# PowerBoard.net
KiCad netlist of a schematic drawn in Altium Designer
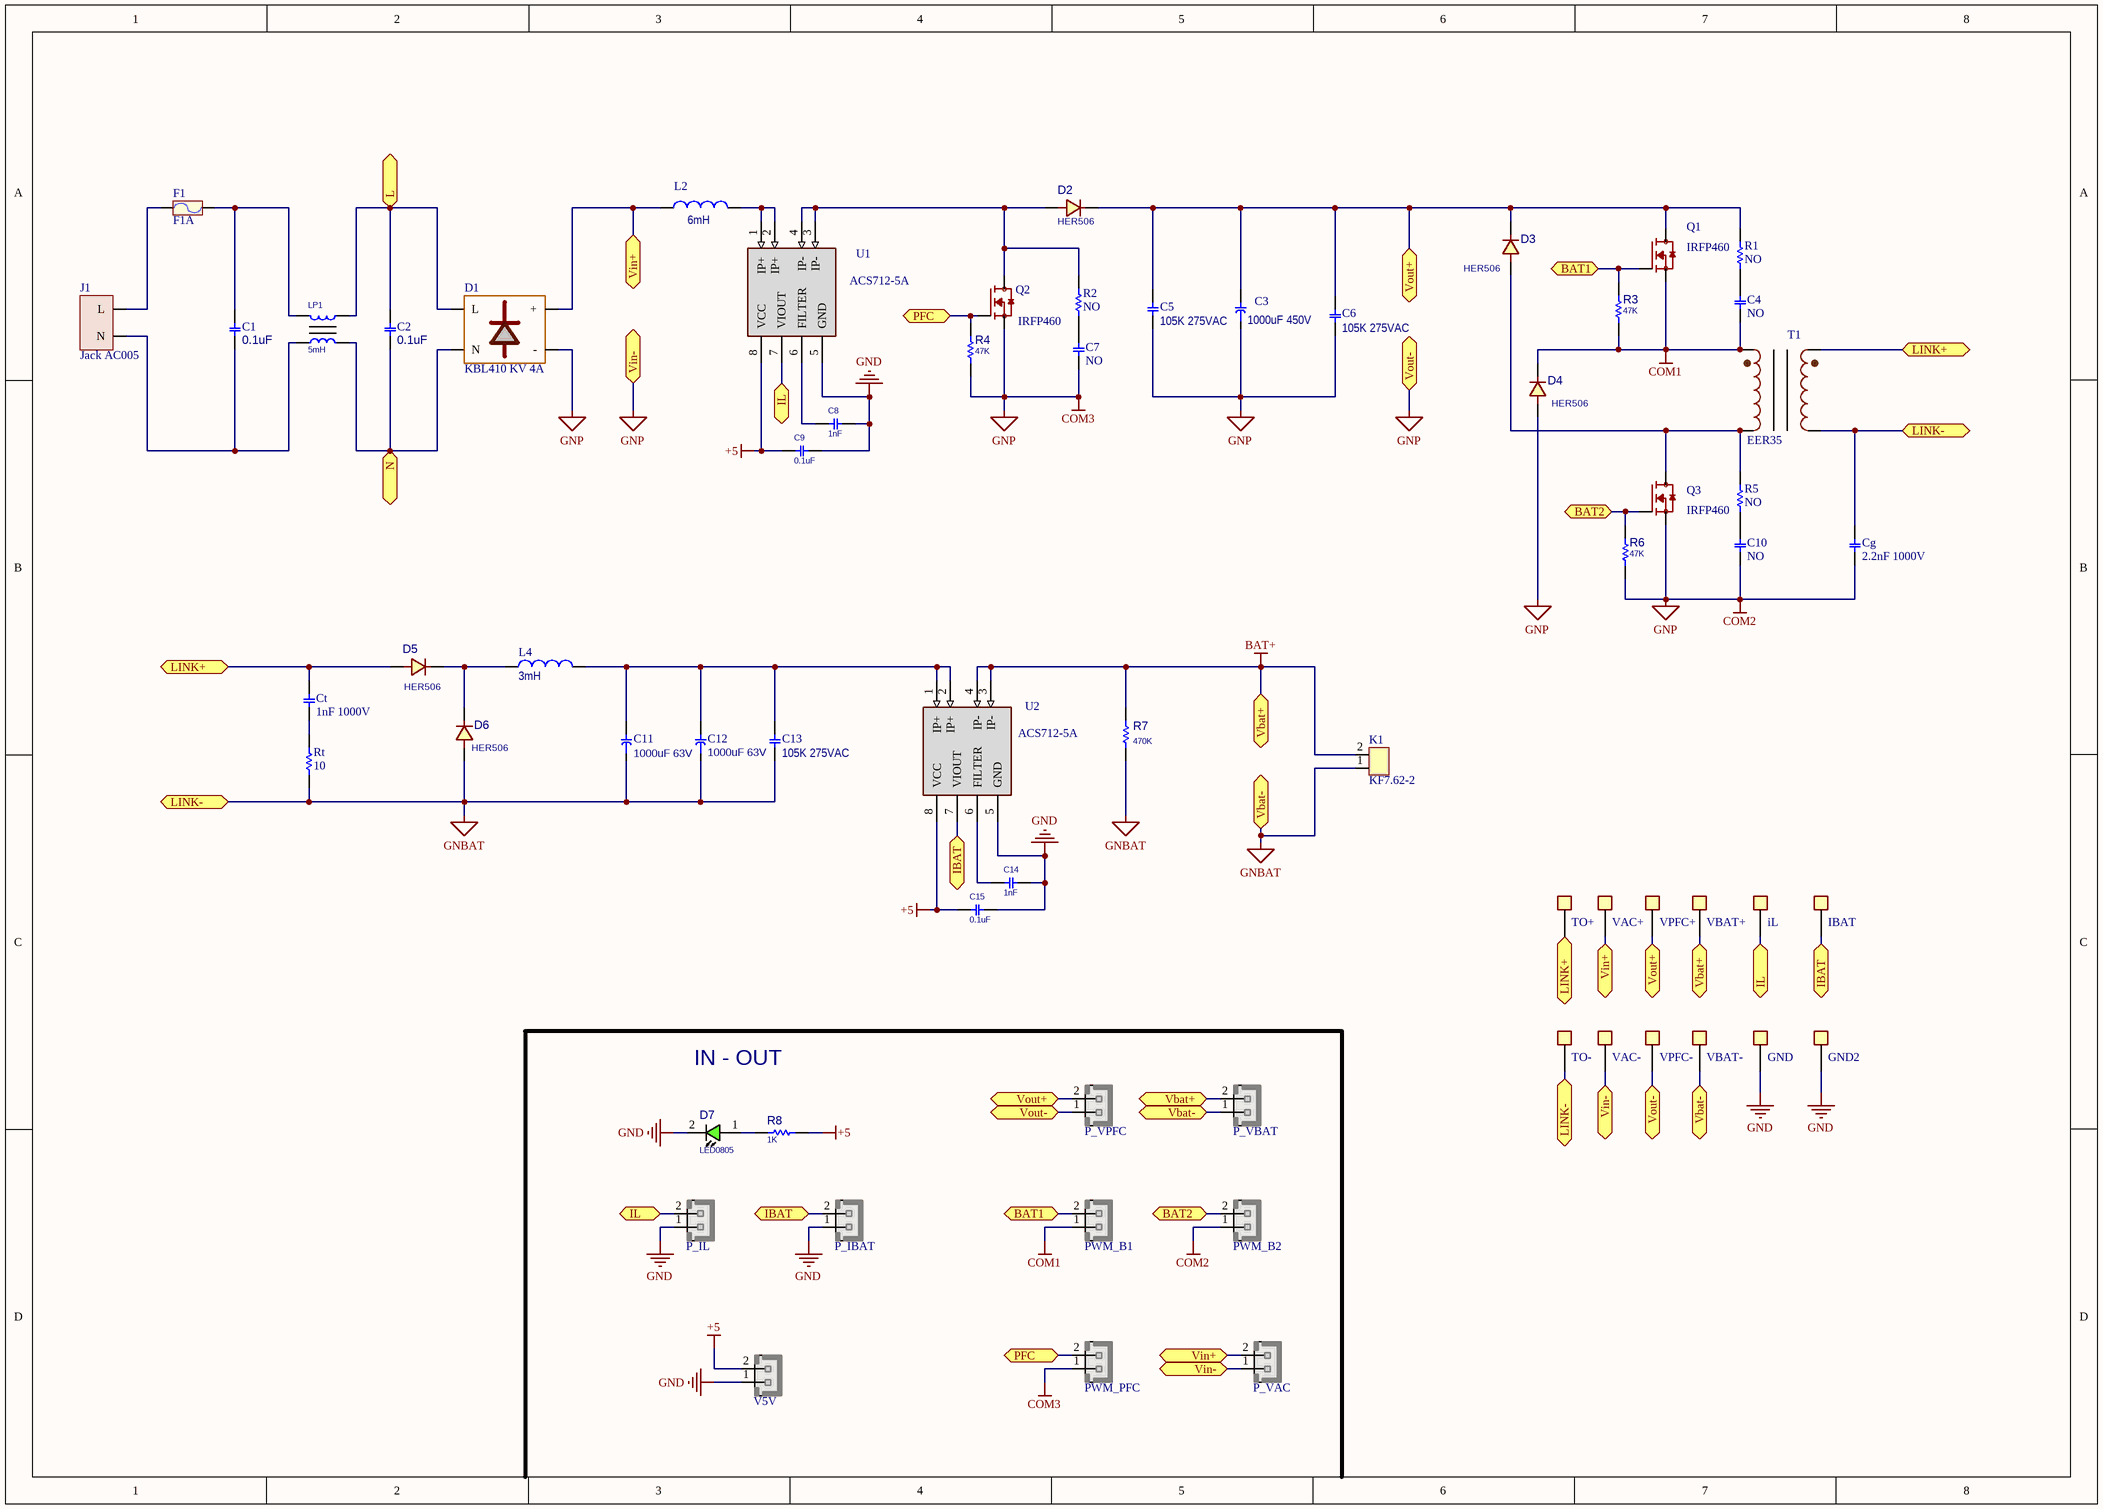
[diagram p0: PowerBoard.SchDoc]

(export (version "E")
  (design (tool "Eeschema 10.0.6"))
  (components
    (comp (ref "C1")
      (value "0.1uF")
      (footprint "CAP P=15MM")
      (description "100nF 104J 275VAC")
      (fields (field (name "COPYRIGHT") "VanDungEvn"))
      (libsource (lib "IoT") (part "CAP Keo"))
    )
    (comp (ref "C2")
      (value "0.1uF")
      (footprint "CAP P=15MM")
      (description "100nF 104J 275VAC")
      (fields (field (name "COPYRIGHT") "VanDungEvn"))
      (libsource (lib "IoT") (part "CAP Keo"))
    )
    (comp (ref "C3")
      (value "1000uF 450V")
      (footprint "cap dxl 35x45")
      (description "CAP DIP")
      (libsource (lib "IoT") (part "CAP DIP"))
    )
    (comp (ref "C4")
      (value "NO")
      (footprint "CAP CBB22 100nF/630V")
      (description "CAP Keo")
      (fields (field (name "COPYRIGHT") "VanDungEvn"))
      (libsource (lib "IoT") (part "CAP Keo"))
    )
    (comp (ref "C5")
      (value "105K 275VAC")
      (footprint "CAP P=22.5mm Len=26.5")
      (description "CAP Keo")
      (fields (field (name "COPYRIGHT") "VanDungEvn"))
      (libsource (lib "IoT") (part "CAP Keo"))
    )
    (comp (ref "C6")
      (value "105K 275VAC")
      (footprint "CAP P=22.5mm Len=26.5")
      (description "CAP Keo")
      (fields (field (name "COPYRIGHT") "VanDungEvn"))
      (libsource (lib "IoT") (part "CAP Keo"))
    )
    (comp (ref "C7")
      (value "NO")
      (footprint "CAP CBB22 100nF/630V")
      (description "CAP Keo")
      (fields (field (name "COPYRIGHT") "VanDungEvn"))
      (libsource (lib "IoT") (part "CAP Keo"))
    )
    (comp (ref "C8")
      (value "1nF")
      (footprint "cap_0805")
      (description "CAP SMD")
      (fields (field (name "MANF_P#") "MANF_PART#"))
      (libsource (lib "IoT") (part "CAP SMD"))
    )
    (comp (ref "C9")
      (value "0.1uF")
      (footprint "cap_0805")
      (description "CAP SMD")
      (fields (field (name "MANF_P#") "MANF_PART#"))
      (libsource (lib "IoT") (part "CAP SMD"))
    )
    (comp (ref "C10")
      (value "NO")
      (footprint "CAP CBB22 100nF/630V")
      (description "CAP Keo")
      (fields (field (name "COPYRIGHT") "VanDungEvn"))
      (libsource (lib "IoT") (part "CAP Keo"))
    )
    (comp (ref "C11")
      (value "1000uF 63V")
      (footprint "CAP DxL 16x25")
      (description "CAP DIP")
      (libsource (lib "IoT") (part "CAP DIP"))
    )
    (comp (ref "C12")
      (value "1000uF 63V")
      (footprint "CAP DxL 16x25")
      (description "CAP DIP")
      (libsource (lib "IoT") (part "CAP DIP"))
    )
    (comp (ref "C13")
      (value "105K 275VAC")
      (footprint "CAP P=22.5mm Len=26.5")
      (description "CAP Keo")
      (fields (field (name "COPYRIGHT") "VanDungEvn"))
      (libsource (lib "IoT") (part "CAP Keo"))
    )
    (comp (ref "C14")
      (value "1nF")
      (footprint "cap_0805")
      (description "CAP SMD")
      (fields (field (name "MANF_P#") "MANF_PART#"))
      (libsource (lib "IoT") (part "CAP SMD"))
    )
    (comp (ref "C15")
      (value "0.1uF")
      (footprint "cap_0805")
      (description "CAP SMD")
      (fields (field (name "MANF_P#") "MANF_PART#"))
      (libsource (lib "IoT") (part "CAP SMD"))
    )
    (comp (ref "Cg")
      (value "2.2nF 1000V")
      (footprint "CAP CERAMIC Blue")
      (description "Tu Gom Xanh 2.2nF 1000V")
      (fields (field (name "COPYRIGHT") "VanDungEvn"))
      (libsource (lib "IoT") (part "CAP Keo"))
    )
    (comp (ref "Ct")
      (value "1nF 1000V")
      (footprint "CAP CERAMIC Blue")
      (description "Tu Gom Xanh 1nF 1000V")
      (fields (field (name "COPYRIGHT") "VanDungEvn"))
      (libsource (lib "IoT") (part "CAP Keo"))
    )
    (comp (ref "D1")
      (value "KBL410 KV 4A")
      (footprint "SIP-4 KBL")
      (description "Diode Bridge 1KV 4A")
      (libsource (lib "IoT") (part "Diode Bridge"))
    )
    (comp (ref "D2")
      (value "HER506")
      (footprint "DIODE DO-201AD")
      (description "DIODE DIP")
      (fields (field (name "MANF") "Kingtronics") (field (name "MANF_P#") "M7"))
      (libsource (lib "IoT") (part "DIODE DIP"))
    )
    (comp (ref "D3")
      (value "HER506")
      (footprint "DIODE DO-201AD")
      (description "DIODE DIP")
      (fields (field (name "MANF") "Kingtronics") (field (name "MANF_P#") "M7"))
      (libsource (lib "IoT") (part "DIODE DIP"))
    )
    (comp (ref "D4")
      (value "HER506")
      (footprint "DIODE DO-201AD")
      (description "DIODE DIP")
      (fields (field (name "MANF") "Kingtronics") (field (name "MANF_P#") "M7"))
      (libsource (lib "IoT") (part "DIODE DIP"))
    )
    (comp (ref "D5")
      (value "HER506")
      (footprint "DIODE DO-201AD")
      (description "DIODE DIP")
      (fields (field (name "MANF") "Kingtronics") (field (name "MANF_P#") "M7"))
      (libsource (lib "IoT") (part "DIODE DIP"))
    )
    (comp (ref "D6")
      (value "HER506")
      (footprint "DIODE DO-201AD")
      (description "DIODE DIP")
      (fields (field (name "MANF") "Kingtronics") (field (name "MANF_P#") "M7"))
      (libsource (lib "IoT") (part "DIODE DIP"))
    )
    (comp (ref "D7")
      (value "LED0805")
      (footprint "LED0805")
      (description "LED, SMD, 0805")
      (fields (field (name "MANF") "MANF") (field (name "MANF_P#") "MANF_PART#"))
      (libsource (lib "IoT") (part "LED_SMD_0805"))
    )
    (comp (ref "F1")
      (value "F1A")
      (footprint "FUSE")
      (description "Cau Chi ong Thuy Tinh 3A 5x20mm")
      (fields (field (name "DESIGNED BY") "VanDungEvn"))
      (libsource (lib "IoT") (part "Fuse"))
    )
    (comp (ref "GND")
      (value "test PCB")
      (footprint "Tp_black_1p")
      (description "testpin")
      (libsource (lib "IoT") (part "test PCB"))
    )
    (comp (ref "GND2")
      (value "test PCB")
      (footprint "Tp_black_1p")
      (description "testpin")
      (libsource (lib "IoT") (part "test PCB"))
    )
    (comp (ref "IBAT")
      (value "test PCB")
      (footprint "tp_red_1p")
      (description "testpin")
      (libsource (lib "IoT") (part "test PCB"))
    )
    (comp (ref "iL")
      (value "test PCB")
      (footprint "tp_red_1p")
      (description "testpin")
      (libsource (lib "IoT") (part "test PCB"))
    )
    (comp (ref "J1")
      (value "Jack AC005")
      (footprint "AC005")
      (description "AC005 5A")
      (libsource (lib "IoT") (part "Jack AC"))
    )
    (comp (ref "K1")
      (value "KF7.62-2")
      (footprint "KF_2PIN")
      (description "KF_2PIN")
      (libsource (lib "IoT") (part "KF_2PIN"))
    )
    (comp (ref "L2")
      (value "6mH")
      (footprint "IND 40P")
      (description "IND DIP")
      (fields
        (field (name "MANUFACTURER") "Murata")
        (field (name "MANUFACTURER PART NUMBER") "LQW15AN2N2G80D")
      )
      (libsource (lib "IoT") (part "IND DIP"))
    )
    (comp (ref "L4")
      (value "3mH")
      (footprint "IND 40P")
      (description "IND DIP")
      (fields
        (field (name "MANUFACTURER") "Murata")
        (field (name "MANUFACTURER PART NUMBER") "LQW15AN2N2G80D")
      )
      (libsource (lib "IoT") (part "IND DIP"))
    )
    (comp (ref "LP1")
      (value "5mH")
      (footprint "Filter Inductor")
      (description "5mH UU9.8-502")
      (fields (field (name "MANF") "Coilcraft") (field (name "MANF_P#") "XAL1030-301MEC"))
      (libsource (lib "IoT") (part "IND Filter 15mH"))
    )
    (comp (ref "PWM_B1")
      (value "HHDR_2")
      (footprint "VH-2")
      (description "VH-2")
      (libsource (lib "IoT") (part "VH-2"))
    )
    (comp (ref "PWM_B2")
      (value "HHDR_2")
      (footprint "VH-2")
      (description "VH-2")
      (libsource (lib "IoT") (part "VH-2"))
    )
    (comp (ref "PWM_PFC")
      (value "HHDR_2")
      (footprint "VH-2")
      (description "VH-2")
      (libsource (lib "IoT") (part "VH-2"))
    )
    (comp (ref "P_IBAT")
      (value "HHDR_2")
      (footprint "XH_2")
      (description "XH 2 JST-XH pitch: 2.5mm")
      (libsource (lib "IoT") (part "XH_2"))
    )
    (comp (ref "P_IL")
      (value "HHDR_2")
      (footprint "XH_2")
      (description "XH 2 JST-XH pitch: 2.5mm")
      (libsource (lib "IoT") (part "XH_2"))
    )
    (comp (ref "P_VAC")
      (value "HHDR_2")
      (footprint "VH-2")
      (description "VH-2")
      (libsource (lib "IoT") (part "VH-2"))
    )
    (comp (ref "P_VBAT")
      (value "HHDR_2")
      (footprint "VH-2")
      (description "VH-2")
      (libsource (lib "IoT") (part "VH-2"))
    )
    (comp (ref "P_VPFC")
      (value "HHDR_2")
      (footprint "VH-2")
      (description "VH-2")
      (libsource (lib "IoT") (part "VH-2"))
    )
    (comp (ref "Q1")
      (value "IRFP460")
      (footprint "TO-247 - HS342512")
      (description "MOSFET N-Channel 500 V 20A (Tc) 280W (Tc) Through Hole TO-247AC")
      (fields (field (name "MF") "Vishay Siliconix"))
      (libsource (lib "IoT") (part "MOSFET IRFP460"))
    )
    (comp (ref "Q2")
      (value "IRFP460")
      (footprint "TO-247 - HS342512")
      (description "MOSFET N-Channel 500 V 20A (Tc) 280W (Tc) Through Hole TO-247AC")
      (fields (field (name "MF") "Vishay Siliconix"))
      (libsource (lib "IoT") (part "MOSFET IRFP460"))
    )
    (comp (ref "Q3")
      (value "IRFP460")
      (footprint "TO-247 - HS342512")
      (description "MOSFET N-Channel 500 V 20A (Tc) 280W (Tc) Through Hole TO-247AC")
      (fields (field (name "MF") "Vishay Siliconix"))
      (libsource (lib "IoT") (part "MOSFET IRFP460"))
    )
    (comp (ref "R1")
      (value "NO")
      (footprint "R-2W")
      (description "RES DIP")
      (libsource (lib "IoT") (part "RES DIP"))
    )
    (comp (ref "R2")
      (value "NO")
      (footprint "R-2W")
      (description "RES DIP")
      (libsource (lib "IoT") (part "RES DIP"))
    )
    (comp (ref "R3")
      (value "47K")
      (footprint "R0805")
      (description "RES SMD")
      (fields (field (name "MANF_P#") "WSLP0805R0100FEA") (field (name "MANF") "VISHAY"))
      (libsource (lib "IoT") (part "RES SMD"))
    )
    (comp (ref "R4")
      (value "47K")
      (footprint "R0805")
      (description "RES SMD")
      (fields (field (name "MANF_P#") "WSLP0805R0100FEA") (field (name "MANF") "VISHAY"))
      (libsource (lib "IoT") (part "RES SMD"))
    )
    (comp (ref "R5")
      (value "NO")
      (footprint "R-2W")
      (description "RES DIP")
      (libsource (lib "IoT") (part "RES DIP"))
    )
    (comp (ref "R6")
      (value "47K")
      (footprint "R0805")
      (description "RES SMD")
      (fields (field (name "MANF_P#") "WSLP0805R0100FEA") (field (name "MANF") "VISHAY"))
      (libsource (lib "IoT") (part "RES SMD"))
    )
    (comp (ref "R7")
      (value "470K")
      (footprint "R1206")
      (description "RES SMD")
      (fields (field (name "MANF_P#") "WSLP0805R0100FEA") (field (name "MANF") "VISHAY"))
      (libsource (lib "IoT") (part "RES SMD"))
    )
    (comp (ref "R8")
      (value "1K")
      (footprint "R0805")
      (description "RES SMD")
      (fields (field (name "MANF_P#") "WSLP0805R0100FEA") (field (name "MANF") "VISHAY"))
      (libsource (lib "IoT") (part "RES SMD"))
    )
    (comp (ref "Rt")
      (value "10")
      (footprint "R1/4W4")
      (description "10 ohm, 1W")
      (libsource (lib "IoT") (part "RES DIP"))
    )
    (comp (ref "T1")
      (value "EER35")
      (footprint "Pulse Transformer")
      (description "Pulse Transformer")
      (libsource (lib "IoT") (part "Pulse Transformer"))
    )
    (comp (ref "TO+")
      (value "test PCB")
      (footprint "tp_red_1p")
      (description "testpin")
      (libsource (lib "IoT") (part "test PCB"))
    )
    (comp (ref "TO-")
      (value "test PCB")
      (footprint "Tp_black_1p")
      (description "testpin")
      (libsource (lib "IoT") (part "test PCB"))
    )
    (comp (ref "U1")
      (value "ACS712-5A")
      (footprint "IoT:ACS712")
      (description "ACS712ELCTR-T")
      (fields (field (name "MF") "{'manufacturer': u'Allegro'}") (field (name "MP") "ACS712ELCTR-20A-T"))
      (libsource (lib "IoT") (part "ACS712ELCTR-T"))
    )
    (comp (ref "U2")
      (value "ACS712-5A")
      (footprint "IoT:ACS712")
      (description "ACS712ELCTR-T")
      (fields (field (name "MF") "{'manufacturer': u'Allegro'}") (field (name "MP") "ACS712ELCTR-20A-T"))
      (libsource (lib "IoT") (part "ACS712ELCTR-T"))
    )
    (comp (ref "V5V")
      (value "HHDR_2")
      (footprint "VH-2")
      (description "VH-2")
      (libsource (lib "IoT") (part "VH-2"))
    )
    (comp (ref "VAC+")
      (value "test PCB")
      (footprint "tp_red_1p")
      (description "testpin")
      (libsource (lib "IoT") (part "test PCB"))
    )
    (comp (ref "VAC-")
      (value "test PCB")
      (footprint "Tp_black_1p")
      (description "testpin")
      (libsource (lib "IoT") (part "test PCB"))
    )
    (comp (ref "VBAT+")
      (value "test PCB")
      (footprint "tp_red_1p")
      (description "testpin")
      (libsource (lib "IoT") (part "test PCB"))
    )
    (comp (ref "VBAT-")
      (value "test PCB")
      (footprint "Tp_black_1p")
      (description "testpin")
      (libsource (lib "IoT") (part "test PCB"))
    )
    (comp (ref "VPFC+")
      (value "test PCB")
      (footprint "tp_red_1p")
      (description "testpin")
      (libsource (lib "IoT") (part "test PCB"))
    )
    (comp (ref "VPFC-")
      (value "test PCB")
      (footprint "Tp_black_1p")
      (description "testpin")
      (libsource (lib "IoT") (part "test PCB"))
    )
  )
  (nets
    (net (code "1") (name "+5") (class "Default")
      (node (ref "C15") (pin "2") (pinfunction "2_2") (pintype "passive"))
      (node (ref "C9") (pin "2") (pinfunction "2_2") (pintype "passive"))
      (node (ref "R8") (pin "2") (pinfunction "2_2") (pintype "passive"))
      (node (ref "U1") (pin "8") (pinfunction "VCC_8") (pintype "power_in"))
      (node (ref "U2") (pin "8") (pinfunction "VCC_8") (pintype "power_in"))
      (node (ref "V5V") (pin "2") (pinfunction "2_2") (pintype "passive"))
    )
    (net (code "2") (name "/BAT1") (class "Default")
      (node (ref "PWM_B1") (pin "2") (pinfunction "2_2") (pintype "passive"))
      (node (ref "Q1") (pin "1") (pinfunction "G_1") (pintype "passive"))
      (node (ref "R3") (pin "1") (pinfunction "1_1") (pintype "passive"))
    )
    (net (code "3") (name "/BAT2") (class "Default")
      (node (ref "PWM_B2") (pin "2") (pinfunction "2_2") (pintype "passive"))
      (node (ref "Q3") (pin "1") (pinfunction "G_1") (pintype "passive"))
      (node (ref "R6") (pin "1") (pinfunction "1_1") (pintype "passive"))
    )
    (net (code "4") (name "/IBAT") (class "Default")
      (node (ref "IBAT") (pin "1") (pinfunction "1_1") (pintype "power_in"))
      (node (ref "P_IBAT") (pin "2") (pinfunction "2_2") (pintype "passive"))
      (node (ref "U2") (pin "7") (pinfunction "VIOUT_7") (pintype "power_in"))
    )
    (net (code "5") (name "/IL") (class "Default")
      (node (ref "P_IL") (pin "2") (pinfunction "2_2") (pintype "passive"))
      (node (ref "U1") (pin "7") (pinfunction "VIOUT_7") (pintype "power_in"))
      (node (ref "iL") (pin "1") (pinfunction "1_1") (pintype "power_in"))
    )
    (net (code "6") (name "/L") (class "Default")
      (node (ref "C2") (pin "2") (pinfunction "2_2") (pintype "passive"))
      (node (ref "D1") (pin "2") (pinfunction "L_2") (pintype "passive"))
      (node (ref "LP1") (pin "2") (pinfunction "2_2") (pintype "passive"))
    )
    (net (code "7") (name "/LINK+") (class "Default")
      (node (ref "Ct") (pin "2") (pinfunction "2_2") (pintype "passive"))
      (node (ref "D5") (pin "1") (pinfunction "1_1") (pintype "passive"))
      (node (ref "T1") (pin "9") (pinfunction "9_9") (pintype "passive"))
      (node (ref "TO+") (pin "1") (pinfunction "1_1") (pintype "power_in"))
    )
    (net (code "8") (name "/N") (class "Default")
      (node (ref "C2") (pin "1") (pinfunction "1_1") (pintype "passive"))
      (node (ref "D1") (pin "3") (pinfunction "N_3") (pintype "passive"))
      (node (ref "LP1") (pin "4") (pinfunction "4_4") (pintype "passive"))
    )
    (net (code "9") (name "/PFC") (class "Default")
      (node (ref "PWM_PFC") (pin "2") (pinfunction "2_2") (pintype "passive"))
      (node (ref "Q2") (pin "1") (pinfunction "G_1") (pintype "passive"))
      (node (ref "R4") (pin "2") (pinfunction "2_2") (pintype "passive"))
    )
    (net (code "10") (name "/Vin+") (class "Default")
      (node (ref "D1") (pin "1") (pinfunction "+_1") (pintype "passive"))
      (node (ref "L2") (pin "1") (pinfunction "1_1") (pintype "passive"))
      (node (ref "P_VAC") (pin "2") (pinfunction "2_2") (pintype "passive"))
      (node (ref "VAC+") (pin "1") (pinfunction "1_1") (pintype "power_in"))
    )
    (net (code "11") (name "/Vout+") (class "Default")
      (node (ref "C3") (pin "1") (pinfunction "1_1") (pintype "passive"))
      (node (ref "C5") (pin "2") (pinfunction "2_2") (pintype "passive"))
      (node (ref "C6") (pin "2") (pinfunction "2_2") (pintype "passive"))
      (node (ref "D2") (pin "2") (pinfunction "2_2") (pintype "passive"))
      (node (ref "D3") (pin "2") (pinfunction "2_2") (pintype "passive"))
      (node (ref "P_VPFC") (pin "2") (pinfunction "2_2") (pintype "passive"))
      (node (ref "Q1") (pin "2") (pinfunction "D_2") (pintype "passive"))
      (node (ref "R1") (pin "2") (pinfunction "2_2") (pintype "passive"))
      (node (ref "VPFC+") (pin "1") (pinfunction "1_1") (pintype "power_in"))
    )
    (net (code "12") (name "BAT+") (class "Default")
      (node (ref "K1") (pin "2") (pinfunction "2_2") (pintype "passive"))
      (node (ref "P_VBAT") (pin "2") (pinfunction "2_2") (pintype "passive"))
      (node (ref "R7") (pin "2") (pinfunction "2_2") (pintype "passive"))
      (node (ref "U2") (pin "3") (pinfunction "IP-_3") (pintype "input"))
      (node (ref "U2") (pin "4") (pinfunction "IP-_4") (pintype "input"))
      (node (ref "VBAT+") (pin "1") (pinfunction "1_1") (pintype "power_in"))
    )
    (net (code "13") (name "COM1") (class "Default")
      (node (ref "C4") (pin "1") (pinfunction "1_1") (pintype "passive"))
      (node (ref "D4") (pin "2") (pinfunction "2_2") (pintype "passive"))
      (node (ref "PWM_B1") (pin "1") (pinfunction "1_1") (pintype "passive"))
      (node (ref "Q1") (pin "3") (pinfunction "S_3") (pintype "passive"))
      (node (ref "R3") (pin "2") (pinfunction "2_2") (pintype "passive"))
      (node (ref "T1") (pin "2") (pinfunction "2_2") (pintype "passive"))
    )
    (net (code "14") (name "COM2") (class "Default")
      (node (ref "C10") (pin "1") (pinfunction "1_1") (pintype "passive"))
      (node (ref "C3") (pin "2") (pinfunction "2_2") (pintype "passive"))
      (node (ref "C5") (pin "1") (pinfunction "1_1") (pintype "passive"))
      (node (ref "C6") (pin "1") (pinfunction "1_1") (pintype "passive"))
      (node (ref "C7") (pin "1") (pinfunction "1_1") (pintype "passive"))
      (node (ref "Cg") (pin "1") (pinfunction "1_1") (pintype "passive"))
      (node (ref "D1") (pin "4") (pinfunction "-_4") (pintype "passive"))
      (node (ref "D4") (pin "1") (pinfunction "1_1") (pintype "passive"))
      (node (ref "PWM_B2") (pin "1") (pinfunction "1_1") (pintype "passive"))
      (node (ref "PWM_PFC") (pin "1") (pinfunction "1_1") (pintype "passive"))
      (node (ref "P_VAC") (pin "1") (pinfunction "1_1") (pintype "passive"))
      (node (ref "P_VPFC") (pin "1") (pinfunction "1_1") (pintype "passive"))
      (node (ref "Q2") (pin "3") (pinfunction "S_3") (pintype "passive"))
      (node (ref "Q3") (pin "3") (pinfunction "S_3") (pintype "passive"))
      (node (ref "R4") (pin "1") (pinfunction "1_1") (pintype "passive"))
      (node (ref "R6") (pin "2") (pinfunction "2_2") (pintype "passive"))
      (node (ref "VAC-") (pin "1") (pinfunction "1_1") (pintype "power_in"))
      (node (ref "VPFC-") (pin "1") (pinfunction "1_1") (pintype "power_in"))
    )
    (net (code "15") (name "GNBAT") (class "Default")
      (node (ref "C11") (pin "2") (pinfunction "2_2") (pintype "passive"))
      (node (ref "C12") (pin "2") (pinfunction "2_2") (pintype "passive"))
      (node (ref "C13") (pin "1") (pinfunction "1_1") (pintype "passive"))
      (node (ref "Cg") (pin "2") (pinfunction "2_2") (pintype "passive"))
      (node (ref "D6") (pin "1") (pinfunction "1_1") (pintype "passive"))
      (node (ref "K1") (pin "1") (pinfunction "1_1") (pintype "passive"))
      (node (ref "P_VBAT") (pin "1") (pinfunction "1_1") (pintype "passive"))
      (node (ref "R7") (pin "1") (pinfunction "1_1") (pintype "passive"))
      (node (ref "Rt") (pin "1") (pinfunction "1_1") (pintype "passive"))
      (node (ref "T1") (pin "13") (pinfunction "13_13") (pintype "passive"))
      (node (ref "TO-") (pin "1") (pinfunction "1_1") (pintype "power_in"))
      (node (ref "VBAT-") (pin "1") (pinfunction "1_1") (pintype "power_in"))
    )
    (net (code "16") (name "GND") (class "Default")
      (node (ref "C14") (pin "2") (pinfunction "2_2") (pintype "passive"))
      (node (ref "C15") (pin "1") (pinfunction "1_1") (pintype "passive"))
      (node (ref "C8") (pin "2") (pinfunction "2_2") (pintype "passive"))
      (node (ref "C9") (pin "1") (pinfunction "1_1") (pintype "passive"))
      (node (ref "D7") (pin "2") (pinfunction "CATHODE_2") (pintype "passive"))
      (node (ref "GND") (pin "1") (pinfunction "1_1") (pintype "power_in"))
      (node (ref "GND2") (pin "1") (pinfunction "1_1") (pintype "power_in"))
      (node (ref "P_IBAT") (pin "1") (pinfunction "1_1") (pintype "passive"))
      (node (ref "P_IL") (pin "1") (pinfunction "1_1") (pintype "passive"))
      (node (ref "U1") (pin "5") (pinfunction "GND_5") (pintype "power_in"))
      (node (ref "U2") (pin "5") (pinfunction "GND_5") (pintype "power_in"))
      (node (ref "V5V") (pin "1") (pinfunction "1_1") (pintype "passive"))
    )
    (net (code "17") (name "Net-(C1-Pad2)") (class "Default")
      (node (ref "C1") (pin "2") (pinfunction "2_2") (pintype "passive"))
      (node (ref "F1") (pin "2") (pinfunction "2_2") (pintype "passive"))
      (node (ref "LP1") (pin "1") (pinfunction "1_1") (pintype "passive"))
    )
    (net (code "18") (name "Net-(C4-Pad2)") (class "Default")
      (node (ref "C4") (pin "2") (pinfunction "2_2") (pintype "passive"))
      (node (ref "R1") (pin "1") (pinfunction "1_1") (pintype "passive"))
    )
    (net (code "19") (name "Net-(C7-Pad2)") (class "Default")
      (node (ref "C7") (pin "2") (pinfunction "2_2") (pintype "passive"))
      (node (ref "R2") (pin "1") (pinfunction "1_1") (pintype "passive"))
    )
    (net (code "20") (name "Net-(C10-Pad2)") (class "Default")
      (node (ref "C10") (pin "2") (pinfunction "2_2") (pintype "passive"))
      (node (ref "R5") (pin "1") (pinfunction "1_1") (pintype "passive"))
    )
    (net (code "21") (name "Net-(C11-Pad1)") (class "Default")
      (node (ref "C11") (pin "1") (pinfunction "1_1") (pintype "passive"))
      (node (ref "C12") (pin "1") (pinfunction "1_1") (pintype "passive"))
      (node (ref "C13") (pin "2") (pinfunction "2_2") (pintype "passive"))
      (node (ref "L4") (pin "2") (pinfunction "2_2") (pintype "passive"))
      (node (ref "U2") (pin "1") (pinfunction "IP+_1") (pintype "input"))
      (node (ref "U2") (pin "2") (pinfunction "IP+_2") (pintype "input"))
    )
    (net (code "22") (name "Net-(Ct-Pad1)") (class "Default")
      (node (ref "Ct") (pin "1") (pinfunction "1_1") (pintype "passive"))
      (node (ref "Rt") (pin "2") (pinfunction "2_2") (pintype "passive"))
    )
    (net (code "23") (name "Net-(D5-Pad2)") (class "Default")
      (node (ref "D5") (pin "2") (pinfunction "2_2") (pintype "passive"))
      (node (ref "D6") (pin "2") (pinfunction "2_2") (pintype "passive"))
      (node (ref "L4") (pin "1") (pinfunction "1_1") (pintype "passive"))
    )
    (net (code "24") (name "Net-(D7-ANODE)") (class "Default")
      (node (ref "D7") (pin "1") (pinfunction "ANODE_1") (pintype "passive"))
      (node (ref "R8") (pin "1") (pinfunction "1_1") (pintype "passive"))
    )
    (net (code "25") (name "Net-(J1-L)") (class "Default")
      (node (ref "F1") (pin "1") (pinfunction "1_1") (pintype "passive"))
      (node (ref "J1") (pin "1") (pinfunction "L_1") (pintype "passive"))
    )
    (net (code "26") (name "Net-(J1-N)") (class "Default")
      (node (ref "C1") (pin "1") (pinfunction "1_1") (pintype "passive"))
      (node (ref "J1") (pin "2") (pinfunction "N_2") (pintype "passive"))
      (node (ref "LP1") (pin "3") (pinfunction "3_3") (pintype "passive"))
    )
    (net (code "27") (name "Net-(L2-Pad2)") (class "Default")
      (node (ref "L2") (pin "2") (pinfunction "2_2") (pintype "passive"))
      (node (ref "U1") (pin "1") (pinfunction "IP+_1") (pintype "input"))
      (node (ref "U1") (pin "2") (pinfunction "IP+_2") (pintype "input"))
    )
    (net (code "28") (name "Net-(Q2-D)") (class "Default")
      (node (ref "D2") (pin "1") (pinfunction "1_1") (pintype "passive"))
      (node (ref "Q2") (pin "2") (pinfunction "D_2") (pintype "passive"))
      (node (ref "R2") (pin "2") (pinfunction "2_2") (pintype "passive"))
      (node (ref "U1") (pin "3") (pinfunction "IP-_3") (pintype "input"))
      (node (ref "U1") (pin "4") (pinfunction "IP-_4") (pintype "input"))
    )
    (net (code "29") (name "Net-(Q3-D)") (class "Default")
      (node (ref "D3") (pin "1") (pinfunction "1_1") (pintype "passive"))
      (node (ref "Q3") (pin "2") (pinfunction "D_2") (pintype "passive"))
      (node (ref "R5") (pin "2") (pinfunction "2_2") (pintype "passive"))
      (node (ref "T1") (pin "3") (pinfunction "3_3") (pintype "passive"))
    )
    (net (code "30") (name "Net-(U1-FILTER)") (class "Default")
      (node (ref "C8") (pin "1") (pinfunction "1_1") (pintype "passive"))
      (node (ref "U1") (pin "6") (pinfunction "FILTER_6") (pintype "power_in"))
    )
    (net (code "31") (name "Net-(U2-FILTER)") (class "Default")
      (node (ref "C14") (pin "1") (pinfunction "1_1") (pintype "passive"))
      (node (ref "U2") (pin "6") (pinfunction "FILTER_6") (pintype "power_in"))
    )
  )
)
